# FT232R-Breakout_v37.net
KiCad netlist of a schematic drawn in EAGLE
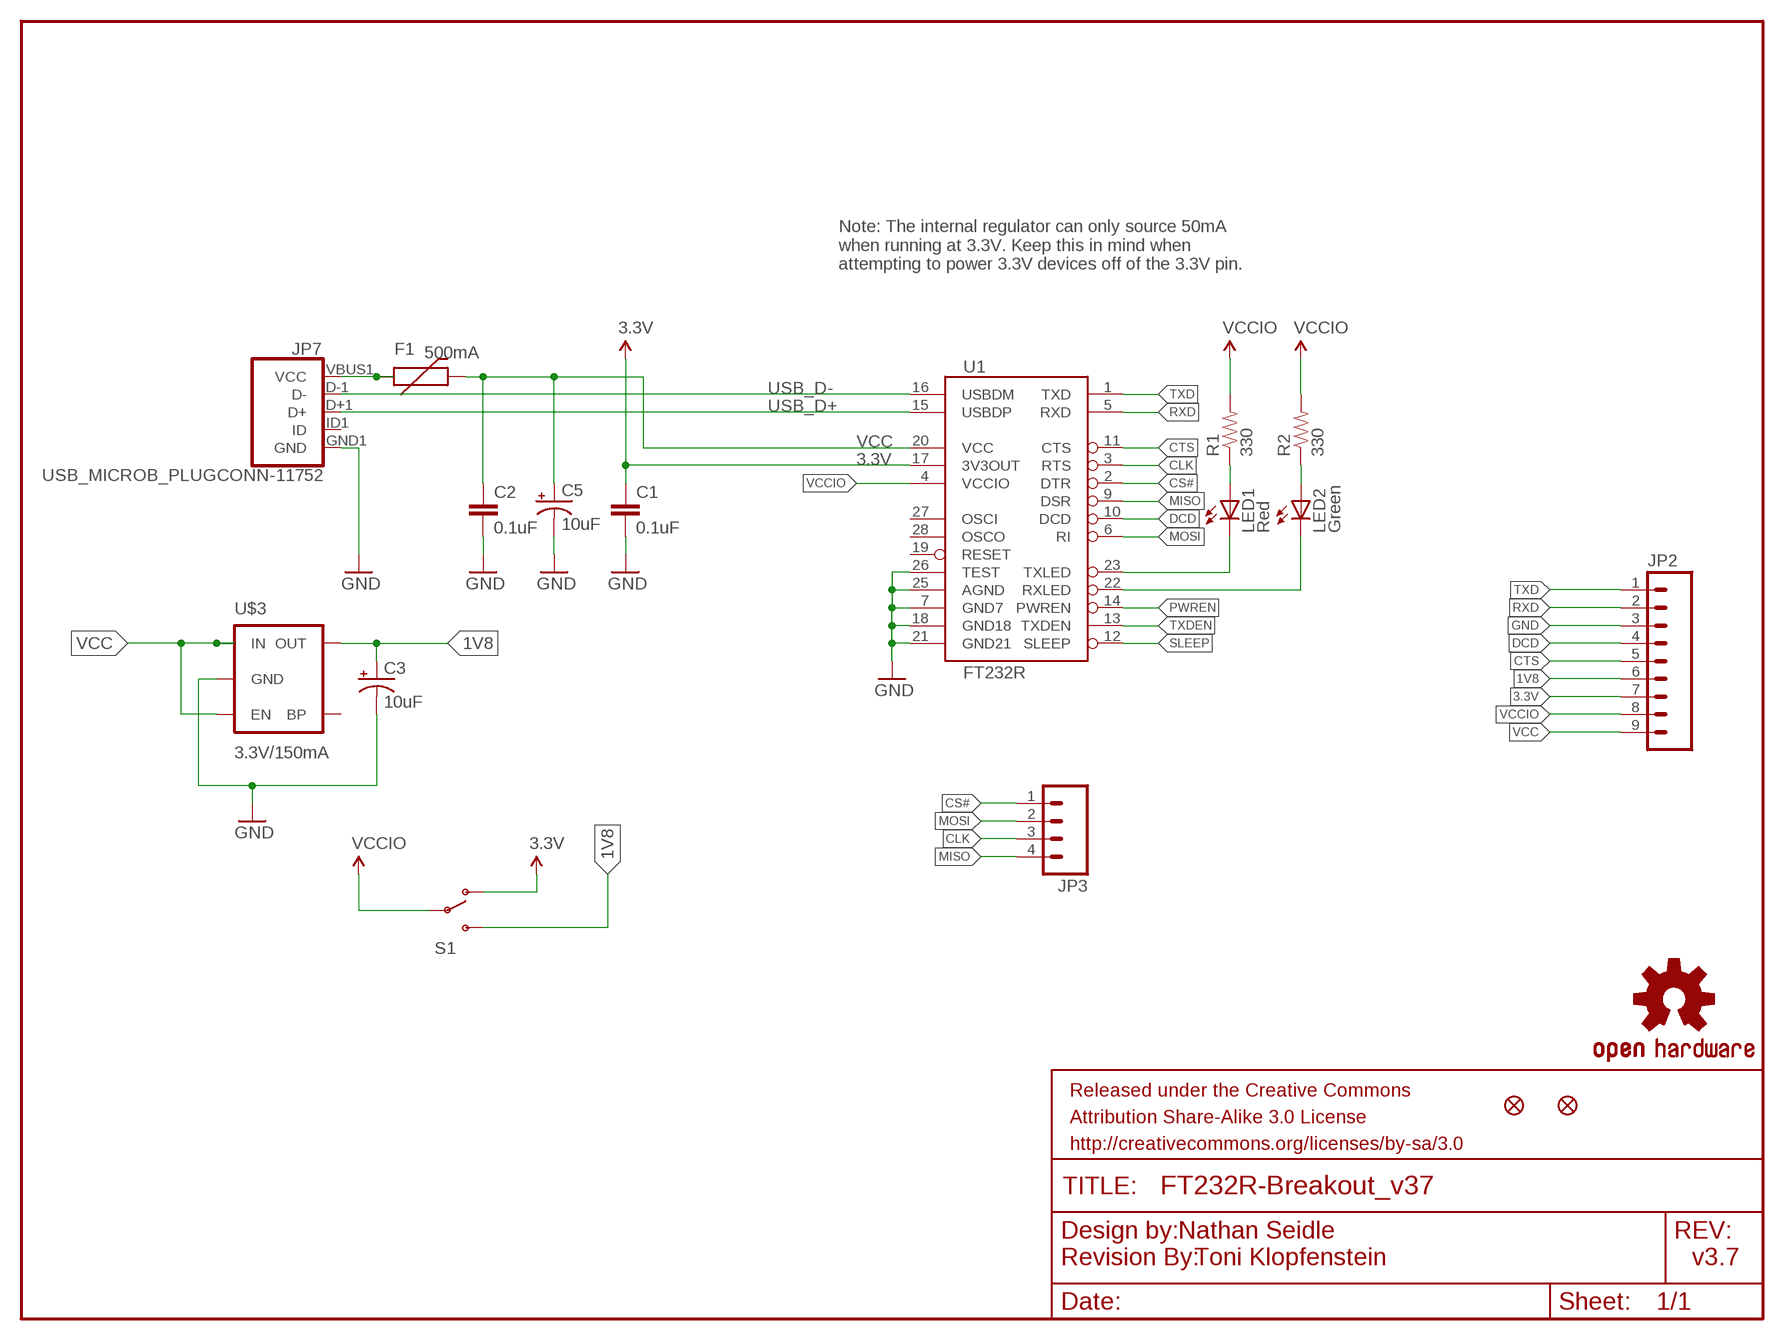
[diagram p0: schematic, sheet 1]

(export (version "E")
  (design (tool "Eeschema 10.0.6"))
  (components
    (comp (ref "C1")
      (value "0.1uF")
      (footprint "eagle-import:0603-CAP")
      (libsource (lib "eagle-import") (part "0.1UF-25V(+80/-20%)(0603)"))
    )
    (comp (ref "C2")
      (value "0.1uF")
      (footprint "eagle-import:0603-CAP")
      (libsource (lib "eagle-import") (part "0.1UF-25V(+80/-20%)(0603)"))
    )
    (comp (ref "C3")
      (value "10uF")
      (footprint "eagle-import:EIA3216")
      (libsource (lib "eagle-import") (part "10UF-16V-10%(TANT)"))
    )
    (comp (ref "C5")
      (value "10uF")
      (footprint "eagle-import:EIA3216")
      (libsource (lib "eagle-import") (part "10UF-16V-10%(TANT)"))
    )
    (comp (ref "F1")
      (value "500mA")
      (footprint "eagle-import:PTC-1206")
      (libsource (lib "eagle-import") (part "PTCSMD"))
    )
    (comp (ref "FRAME1")
      (value "FRAME-LETTER")
      (footprint "eagle-import:CREATIVE_COMMONS")
      (libsource (lib "eagle-import") (part "FRAME-LETTER"))
    )
    (comp (ref "JP2")
      (value "M09")
      (footprint "eagle-import:1X09")
      (libsource (lib "eagle-import") (part "M09"))
    )
    (comp (ref "JP3")
      (value "M04PTH")
      (footprint "eagle-import:1X04")
      (libsource (lib "eagle-import") (part "M04PTH"))
    )
    (comp (ref "JP5")
      (value "FIDUCIAL1X2")
      (footprint "eagle-import:FIDUCIAL-1X2")
      (libsource (lib "eagle-import") (part "FIDUCIAL1X2"))
    )
    (comp (ref "JP6")
      (value "FIDUCIAL1X2")
      (footprint "eagle-import:FIDUCIAL-1X2")
      (libsource (lib "eagle-import") (part "FIDUCIAL1X2"))
    )
    (comp (ref "JP7")
      (value "USB_MICROB_PLUGCONN-11752")
      (footprint "eagle-import:USB-B-MICRO-SMD_V03")
      (libsource (lib "eagle-import") (part "USB_MICROB_PLUGCONN-11752"))
    )
    (comp (ref "LED1")
      (value "Red")
      (footprint "eagle-import:LED-0603")
      (libsource (lib "eagle-import") (part "LED-RED0603"))
    )
    (comp (ref "LED2")
      (value "Green")
      (footprint "eagle-import:LED-0603")
      (libsource (lib "eagle-import") (part "LED-GREEN0603"))
    )
    (comp (ref "LOGO1")
      (value "OSHW-LOGOS")
      (footprint "eagle-import:OSHW-LOGO-S")
      (libsource (lib "eagle-import") (part "OSHW-LOGOS"))
    )
    (comp (ref "R1")
      (value "330")
      (footprint "eagle-import:0603-RES")
      (libsource (lib "eagle-import") (part "330OHM1/10W1%(0603)"))
    )
    (comp (ref "R2")
      (value "330")
      (footprint "eagle-import:0603-RES")
      (libsource (lib "eagle-import") (part "330OHM1/10W1%(0603)"))
    )
    (comp (ref "S1")
      (value "SWITCH-SPDTSMD")
      (footprint "eagle-import:AYZ0202")
      (libsource (lib "eagle-import") (part "SWITCH-SPDTSMD"))
    )
    (comp (ref "U$1")
      (value "REVISION")
      (footprint "eagle-import:REVISION")
      (libsource (lib "eagle-import") (part "REVISION"))
    )
    (comp (ref "U$3")
      (value "3.3V/150mA")
      (footprint "eagle-import:SOT23-5")
      (libsource (lib "eagle-import") (part "V_REG_MIC52053.3V"))
    )
    (comp (ref "U1")
      (value "FT232R")
      (footprint "eagle-import:SSOP28DB")
      (libsource (lib "eagle-import") (part "FT232RLSSOP"))
    )
  )
  (nets
    (net (code "1") (name "/USB_D+") (class "Default")
      (node (ref "JP7") (pin "D+1") (pinfunction "D+_D+1") (pintype "bidirectional"))
      (node (ref "U1") (pin "15") (pinfunction "USBDP_15") (pintype "bidirectional"))
    )
    (net (code "2") (name "/USB_D-") (class "Default")
      (node (ref "JP7") (pin "D-1") (pinfunction "D-_D-1") (pintype "bidirectional"))
      (node (ref "U1") (pin "16") (pinfunction "USBDM_16") (pintype "bidirectional"))
    )
    (net (code "3") (name "1V8") (class "Default")
      (node (ref "C3") (pin "A") (pinfunction "+_A") (pintype "passive"))
      (node (ref "JP2") (pin "6") (pinfunction "6_6") (pintype "passive"))
      (node (ref "S1") (pin "3") (pinfunction "S_3") (pintype "passive"))
      (node (ref "U$3") (pin "5") (pinfunction "OUT_5") (pintype "passive"))
    )
    (net (code "4") (name "3.3V") (class "Default")
      (node (ref "C1") (pin "1") (pinfunction "1_1") (pintype "passive"))
      (node (ref "JP2") (pin "7") (pinfunction "7_7") (pintype "passive"))
      (node (ref "S1") (pin "1") (pinfunction "O_1") (pintype "passive"))
      (node (ref "U1") (pin "17") (pinfunction "3V3OUT_17") (pintype "output"))
    )
    (net (code "5") (name "CLK") (class "Default")
      (node (ref "JP3") (pin "3") (pinfunction "3_3") (pintype "passive"))
      (node (ref "U1") (pin "3") (pinfunction "RTS_3") (pintype "output"))
    )
    (net (code "6") (name "CS#") (class "Default")
      (node (ref "JP3") (pin "1") (pinfunction "1_1") (pintype "passive"))
      (node (ref "U1") (pin "2") (pinfunction "DTR_2") (pintype "output"))
    )
    (net (code "7") (name "CTS") (class "Default")
      (node (ref "JP2") (pin "5") (pinfunction "5_5") (pintype "passive"))
      (node (ref "U1") (pin "11") (pinfunction "CTS_11") (pintype "input"))
    )
    (net (code "8") (name "DCD") (class "Default")
      (node (ref "JP2") (pin "4") (pinfunction "4_4") (pintype "passive"))
      (node (ref "U1") (pin "10") (pinfunction "DCD_10") (pintype "input"))
    )
    (net (code "9") (name "GND") (class "Default")
      (node (ref "C1") (pin "2") (pinfunction "2_2") (pintype "passive"))
      (node (ref "C2") (pin "2") (pinfunction "2_2") (pintype "passive"))
      (node (ref "C3") (pin "C") (pinfunction "-_C") (pintype "passive"))
      (node (ref "C5") (pin "C") (pinfunction "-_C") (pintype "passive"))
      (node (ref "JP2") (pin "3") (pinfunction "3_3") (pintype "passive"))
      (node (ref "JP7") (pin "GND1") (pinfunction "GND_GND1") (pintype "bidirectional"))
      (node (ref "U$3") (pin "2") (pinfunction "GND_2") (pintype "input"))
      (node (ref "U1") (pin "18") (pinfunction "GND18_18") (pintype "power_in"))
      (node (ref "U1") (pin "21") (pinfunction "GND21_21") (pintype "power_in"))
      (node (ref "U1") (pin "25") (pinfunction "AGND_25") (pintype "power_in"))
      (node (ref "U1") (pin "26") (pinfunction "TEST_26") (pintype "input"))
      (node (ref "U1") (pin "7") (pinfunction "GND7_7") (pintype "power_in"))
    )
    (net (code "10") (name "MISO") (class "Default")
      (node (ref "JP3") (pin "4") (pinfunction "4_4") (pintype "passive"))
      (node (ref "U1") (pin "9") (pinfunction "DSR_9") (pintype "input"))
    )
    (net (code "11") (name "MOSI") (class "Default")
      (node (ref "JP3") (pin "2") (pinfunction "2_2") (pintype "passive"))
      (node (ref "U1") (pin "6") (pinfunction "RI_6") (pintype "input"))
    )
    (net (code "12") (name "Net-(JP7-VCC)") (class "Default")
      (node (ref "F1") (pin "1") (pinfunction "1_1") (pintype "bidirectional"))
      (node (ref "JP7") (pin "VBUS1") (pinfunction "VCC_VBUS1") (pintype "bidirectional"))
    )
    (net (code "13") (name "Net-(LED1-PadA)") (class "Default")
      (node (ref "LED1") (pin "A") (pinfunction "A_A") (pintype "passive"))
      (node (ref "R1") (pin "1") (pinfunction "1_1") (pintype "passive"))
    )
    (net (code "14") (name "Net-(LED2-PadA)") (class "Default")
      (node (ref "LED2") (pin "A") (pinfunction "A_A") (pintype "passive"))
      (node (ref "R2") (pin "1") (pinfunction "1_1") (pintype "passive"))
    )
    (net (code "15") (name "Net-(U1-RXLED)") (class "Default")
      (node (ref "LED2") (pin "C") (pinfunction "C_C") (pintype "passive"))
      (node (ref "U1") (pin "22") (pinfunction "RXLED_22") (pintype "input"))
    )
    (net (code "16") (name "Net-(U1-TXLED)") (class "Default")
      (node (ref "LED1") (pin "C") (pinfunction "C_C") (pintype "passive"))
      (node (ref "U1") (pin "23") (pinfunction "TXLED_23") (pintype "input"))
    )
    (net (code "17") (name "PWREN") (class "Default")
      (node (ref "U1") (pin "14") (pinfunction "PWREN_14") (pintype "input"))
    )
    (net (code "18") (name "RXD") (class "Default")
      (node (ref "JP2") (pin "2") (pinfunction "2_2") (pintype "passive"))
      (node (ref "U1") (pin "5") (pinfunction "RXD_5") (pintype "input"))
    )
    (net (code "19") (name "SLEEP") (class "Default")
      (node (ref "U1") (pin "12") (pinfunction "SLEEP_12") (pintype "input"))
    )
    (net (code "20") (name "TXD") (class "Default")
      (node (ref "JP2") (pin "1") (pinfunction "1_1") (pintype "passive"))
      (node (ref "U1") (pin "1") (pinfunction "TXD_1") (pintype "output"))
    )
    (net (code "21") (name "TXDEN") (class "Default")
      (node (ref "U1") (pin "13") (pinfunction "TXDEN_13") (pintype "input"))
    )
    (net (code "22") (name "VCC") (class "Default")
      (node (ref "C2") (pin "1") (pinfunction "1_1") (pintype "passive"))
      (node (ref "C5") (pin "A") (pinfunction "+_A") (pintype "passive"))
      (node (ref "F1") (pin "2") (pinfunction "2_2") (pintype "bidirectional"))
      (node (ref "JP2") (pin "9") (pinfunction "9_9") (pintype "passive"))
      (node (ref "U$3") (pin "1") (pinfunction "IN_1") (pintype "input"))
      (node (ref "U$3") (pin "3") (pinfunction "EN_3") (pintype "input"))
      (node (ref "U1") (pin "20") (pinfunction "VCC_20") (pintype "power_in"))
    )
    (net (code "23") (name "VCCIO") (class "Default")
      (node (ref "JP2") (pin "8") (pinfunction "8_8") (pintype "passive"))
      (node (ref "R1") (pin "2") (pinfunction "2_2") (pintype "passive"))
      (node (ref "R2") (pin "2") (pinfunction "2_2") (pintype "passive"))
      (node (ref "S1") (pin "2") (pinfunction "P_2") (pintype "passive"))
      (node (ref "U1") (pin "4") (pinfunction "VCCIO_4") (pintype "power_in"))
    )
    (net (code "24") (name "unconnected-(JP7-ID-PadID1)") (class "Default")
      (node (ref "JP7") (pin "ID1") (pinfunction "ID_ID1") (pintype "bidirectional"))
    )
    (net (code "25") (name "unconnected-(U$3-BP-Pad4)") (class "Default")
      (node (ref "U$3") (pin "4") (pinfunction "BP_4") (pintype "input"))
    )
    (net (code "26") (name "unconnected-(U1-OSCI-Pad27)") (class "Default")
      (node (ref "U1") (pin "27") (pinfunction "OSCI_27") (pintype "input"))
    )
    (net (code "27") (name "unconnected-(U1-OSCO-Pad28)") (class "Default")
      (node (ref "U1") (pin "28") (pinfunction "OSCO_28") (pintype "output"))
    )
    (net (code "28") (name "unconnected-(U1-RESET-Pad19)") (class "Default")
      (node (ref "U1") (pin "19") (pinfunction "RESET_19") (pintype "input"))
    )
  )
)
